# PUSHBUTTONS.net
KiCad netlist of a schematic drawn in Altium Designer
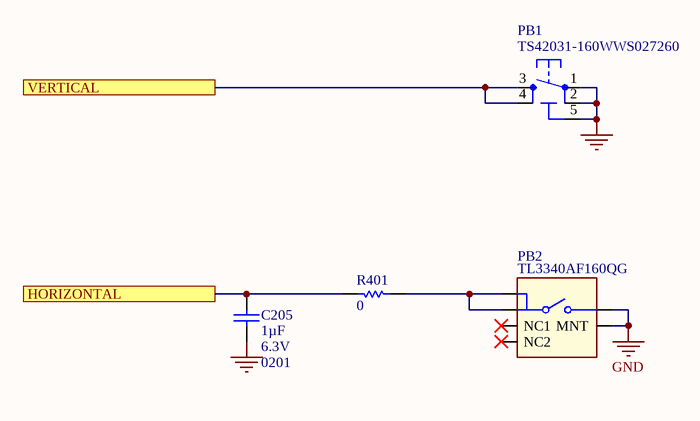
[diagram p0: PUSHBUTTONS.SchDoc]

(export (version "E")
  (design (tool "Eeschema 10.0.6"))
  (components
    (comp (ref "C205")
      (value "1µF")
      (footprint "CAP-0201")
      (description "CAP CHIP 0201 1uF 20% 6.3V X5R")
      (fields
        (field (name "VOLTAGE") "6.3V")
        (field (name "TOLERANCE") "20%")
        (field (name "PART NUMBER") "GRM033R60J105MEA2D")
        (field (name "CASE CODE (IMPERIAL)") "0201")
      )
      (libsource (lib "Clean") (part "CAP"))
    )
    (comp (ref "PB1")
      (value "TS42031-160WWS027260")
      (footprint "TS42")
      (description "PUSHBUTTON SMD 6x6 5 PINS")
      (fields (field (name "MANUFACTURER") "C&K"))
      (libsource (lib "Clean") (part "TS42031-160WWS027260"))
    )
    (comp (ref "PB2")
      (value "TL3340AF160QG")
      (footprint "TL3340AF160QG-Footprint-1")
      (description "PUSHBUTTON SMD VERTICAL ANCHORS 4x3.4mm")
      (fields (field (name "MANUFACTURER") "E-Switch"))
      (libsource (lib "Clean") (part "TL3340AF160QG"))
    )
    (comp (ref "R401")
      (value "0")
      (footprint "RES-0201")
      (description "RES CHIP 0201 0R")
      (fields (field (name "PART NUMBER") "CRCW02010000Z0ED") (field (name "TOLERANCE") "0%"))
      (libsource (lib "Clean") (part "RES"))
    )
  )
  (nets
    (net (code "1") (name "/HORIZONTAL") (class "Default")
      (node (ref "C205") (pin "2") (pinfunction "2_2") (pintype "passive"))
      (node (ref "R401") (pin "1") (pinfunction "1_1") (pintype "passive"))
    )
    (net (code "2") (name "/VERTICAL") (class "Default")
      (node (ref "PB1") (pin "3") (pinfunction "3_3") (pintype "passive"))
      (node (ref "PB1") (pin "4") (pinfunction "4_4") (pintype "passive"))
    )
    (net (code "3") (name "GND") (class "Default")
      (node (ref "C205") (pin "1") (pinfunction "1_1") (pintype "passive"))
      (node (ref "PB1") (pin "1") (pinfunction "1_1") (pintype "passive"))
      (node (ref "PB1") (pin "2") (pinfunction "2_2") (pintype "passive"))
      (node (ref "PB1") (pin "5") (pinfunction "5-GND_5") (pintype "power_in"))
      (node (ref "PB2") (pin "2") (pinfunction "2_2") (pintype "passive"))
      (node (ref "PB2") (pin "MNT") (pinfunction "MNT_MNT") (pintype "passive"))
    )
    (net (code "4") (name "Net-(PB2-Pad1)") (class "Default")
      (node (ref "PB2") (pin "1") (pinfunction "1_1") (pintype "passive"))
      (node (ref "PB2") (pin "3") (pinfunction "3_3") (pintype "passive"))
      (node (ref "R401") (pin "2") (pinfunction "2_2") (pintype "passive"))
    )
    (net (code "5") (name "unconnected-(PB2-PadNC1)") (class "Default")
      (node (ref "PB2") (pin "NC1") (pinfunction "NC1_NC1") (pintype "passive+no_connect"))
    )
    (net (code "6") (name "unconnected-(PB2-PadNC2)") (class "Default")
      (node (ref "PB2") (pin "NC2") (pinfunction "NC2_NC2") (pintype "passive+no_connect"))
    )
  )
)
